# minimal_terminalv2.net
KiCad netlist of a schematic drawn in EAGLE
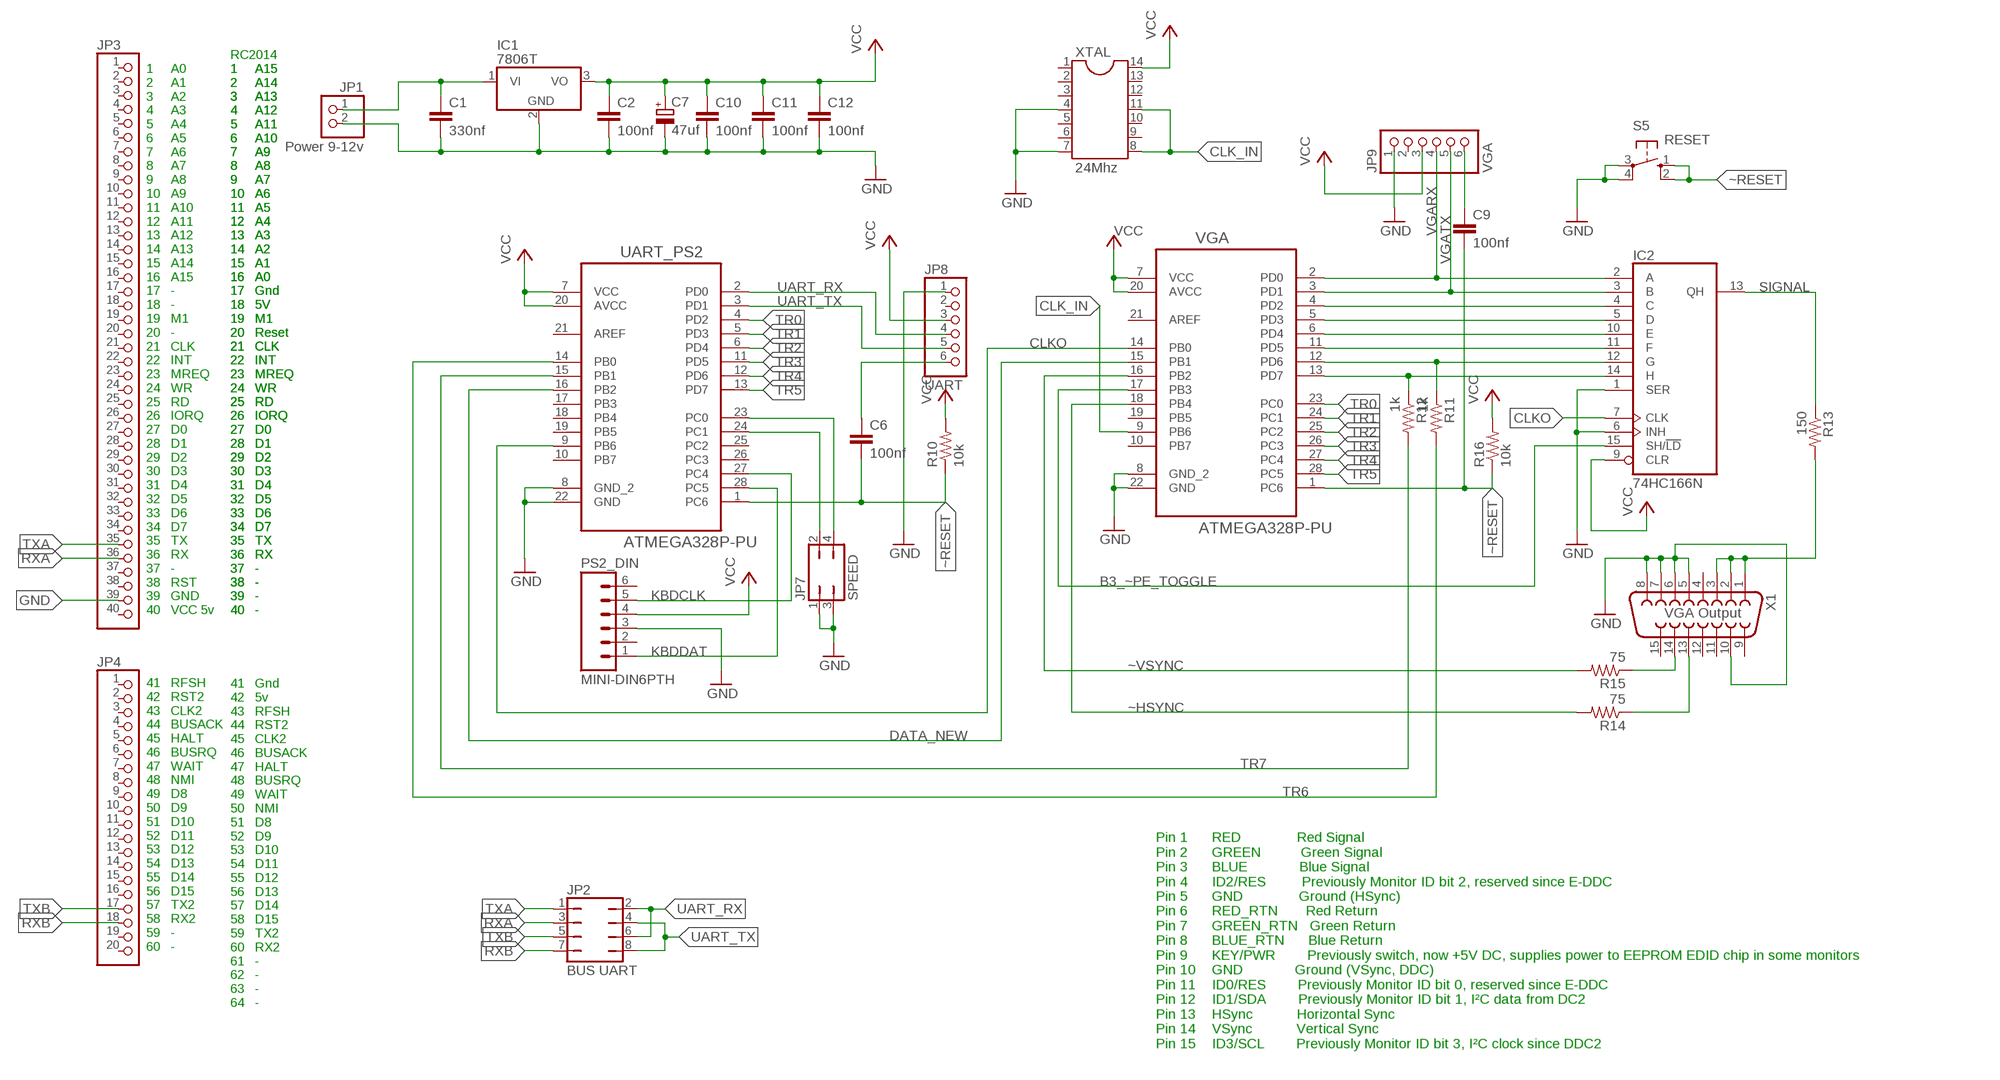
[diagram p0: schematic, sheet 1]

(export (version "E")
  (design (tool "Eeschema 10.0.6"))
  (components
    (comp (ref "C1")
      (value "330nf")
      (footprint "eagle-import:C2.5-3")
      (libsource (lib "eagle-import") (part "C2,5-3"))
    )
    (comp (ref "C2")
      (value "100nf")
      (footprint "eagle-import:C2.5-3")
      (libsource (lib "eagle-import") (part "C2,5-3"))
    )
    (comp (ref "C6")
      (value "100nf")
      (footprint "eagle-import:C2.5-3")
      (libsource (lib "eagle-import") (part "C2,5-3"))
    )
    (comp (ref "C7")
      (value "47uf")
      (footprint "eagle-import:E2,5-6")
      (libsource (lib "eagle-import") (part "CPOL-EUE2.5-6"))
    )
    (comp (ref "C9")
      (value "100nf")
      (footprint "eagle-import:C2.5-3")
      (libsource (lib "eagle-import") (part "C2,5-3"))
    )
    (comp (ref "C10")
      (value "100nf")
      (footprint "eagle-import:C2.5-3")
      (libsource (lib "eagle-import") (part "C2,5-3"))
    )
    (comp (ref "C11")
      (value "100nf")
      (footprint "eagle-import:C2.5-3")
      (libsource (lib "eagle-import") (part "C2,5-3"))
    )
    (comp (ref "C12")
      (value "100nf")
      (footprint "eagle-import:C2.5-3")
      (libsource (lib "eagle-import") (part "C2,5-3"))
    )
    (comp (ref "IC1")
      (value "7806T")
      (footprint "eagle-import:TO220H")
      (libsource (lib "eagle-import") (part "78T06"))
    )
    (comp (ref "IC2")
      (value "74HC166N")
      (footprint "eagle-import:DIL16")
      (libsource (lib "eagle-import") (part "74166NHC"))
    )
    (comp (ref "JP1")
      (value "Power 9-12v")
      (footprint "eagle-import:1X02")
      (libsource (lib "eagle-import") (part "PINHD-1X2"))
    )
    (comp (ref "JP2")
      (value "BUS UART")
      (footprint "eagle-import:JP4Q")
      (libsource (lib "eagle-import") (part "JP4Q"))
    )
    (comp (ref "JP3")
      (value "PINHD-1X40")
      (footprint "eagle-import:1X40")
      (libsource (lib "eagle-import") (part "PINHD-1X40"))
    )
    (comp (ref "JP4")
      (value "PINHD-1X20")
      (footprint "eagle-import:1X20")
      (libsource (lib "eagle-import") (part "PINHD-1X20"))
    )
    (comp (ref "JP7")
      (value "SPEED")
      (footprint "eagle-import:JP2Q")
      (libsource (lib "eagle-import") (part "JP2Q"))
    )
    (comp (ref "JP8")
      (value "UART")
      (footprint "eagle-import:1X06")
      (libsource (lib "eagle-import") (part "PINHD-1X6"))
    )
    (comp (ref "JP9")
      (value "VGA")
      (footprint "eagle-import:1X06")
      (libsource (lib "eagle-import") (part "PINHD-1X6"))
    )
    (comp (ref "PS2_DIN")
      (value "MINI-DIN6PTH")
      (footprint "eagle-import:MINI-DIN6")
      (libsource (lib "eagle-import") (part "MINI-DIN6PTH"))
    )
    (comp (ref "R10")
      (value "10k")
      (footprint "eagle-import:0204_7")
      (libsource (lib "eagle-import") (part "R-US_0204/7"))
    )
    (comp (ref "R11")
      (value "1k")
      (footprint "eagle-import:0204_7")
      (libsource (lib "eagle-import") (part "R-US_0204/7"))
    )
    (comp (ref "R12")
      (value "1k")
      (footprint "eagle-import:0204_7")
      (libsource (lib "eagle-import") (part "R-US_0204/7"))
    )
    (comp (ref "R13")
      (value "150")
      (footprint "eagle-import:0204_7")
      (libsource (lib "eagle-import") (part "R-US_0204/7"))
    )
    (comp (ref "R14")
      (value "75")
      (footprint "eagle-import:0204_7")
      (libsource (lib "eagle-import") (part "R-US_0204/7"))
    )
    (comp (ref "R15")
      (value "75")
      (footprint "eagle-import:0204_7")
      (libsource (lib "eagle-import") (part "R-US_0204/7"))
    )
    (comp (ref "R16")
      (value "10k")
      (footprint "eagle-import:0204_7")
      (libsource (lib "eagle-import") (part "R-US_0204/7"))
    )
    (comp (ref "S5")
      (value "RESET")
      (footprint "eagle-import:B3F-10XX")
      (fields (field (name "MPN") "B3F-1000"))
      (libsource (lib "eagle-import") (part "10-XX"))
    )
    (comp (ref "UART_PS2")
      (value "ATMEGA328P-PU")
      (footprint "eagle-import:DIP254P762X457-28")
      (libsource (lib "eagle-import") (part "ATMEGA328P-PU"))
    )
    (comp (ref "VGA")
      (value "ATMEGA328P-PU")
      (footprint "eagle-import:DIP254P762X457-28")
      (libsource (lib "eagle-import") (part "ATMEGA328P-PU"))
    )
    (comp (ref "X1")
      (value "VGA Output")
      (footprint "eagle-import:HDF15H")
      (libsource (lib "eagle-import") (part "F15HDH"))
    )
    (comp (ref "XTAL")
      (value "24Mhz")
      (footprint "eagle-import:SOCKET-14")
      (libsource (lib "eagle-import") (part "DIL14S"))
    )
  )
  (nets
    (net (code "1") (name "/B3_~{PE_TOGGLE}") (class "Default")
      (node (ref "IC2") (pin "15") (pinfunction "SH/~{LD}_15") (pintype "input"))
      (node (ref "VGA") (pin "17") (pinfunction "PB3_17") (pintype "bidirectional"))
    )
    (net (code "2") (name "/DATA_NEW") (class "Default")
      (node (ref "UART_PS2") (pin "16") (pinfunction "PB2_16") (pintype "bidirectional"))
      (node (ref "VGA") (pin "15") (pinfunction "PB1_15") (pintype "bidirectional"))
    )
    (net (code "3") (name "/KBDCLK") (class "Default")
      (node (ref "PS2_DIN") (pin "5") (pinfunction "5_5") (pintype "passive"))
      (node (ref "UART_PS2") (pin "27") (pinfunction "PC4_27") (pintype "bidirectional"))
    )
    (net (code "4") (name "/KBDDAT") (class "Default")
      (node (ref "PS2_DIN") (pin "1") (pinfunction "1_1") (pintype "passive"))
      (node (ref "UART_PS2") (pin "28") (pinfunction "PC5_28") (pintype "bidirectional"))
    )
    (net (code "5") (name "/SIGNAL") (class "Default")
      (node (ref "IC2") (pin "13") (pinfunction "QH_13") (pintype "output"))
      (node (ref "R13") (pin "1") (pinfunction "1_1") (pintype "passive"))
    )
    (net (code "6") (name "/TR6") (class "Default")
      (node (ref "R11") (pin "2") (pinfunction "2_2") (pintype "passive"))
      (node (ref "UART_PS2") (pin "14") (pinfunction "PB0_14") (pintype "bidirectional"))
    )
    (net (code "7") (name "/TR7") (class "Default")
      (node (ref "R12") (pin "2") (pinfunction "2_2") (pintype "passive"))
      (node (ref "UART_PS2") (pin "15") (pinfunction "PB1_15") (pintype "bidirectional"))
    )
    (net (code "8") (name "/VGARX") (class "Default")
      (node (ref "IC2") (pin "2") (pinfunction "A_2") (pintype "input"))
      (node (ref "JP9") (pin "4") (pinfunction "4_4") (pintype "passive"))
      (node (ref "VGA") (pin "2") (pinfunction "PD0_2") (pintype "bidirectional"))
    )
    (net (code "9") (name "/VGATX") (class "Default")
      (node (ref "IC2") (pin "3") (pinfunction "B_3") (pintype "input"))
      (node (ref "JP9") (pin "5") (pinfunction "5_5") (pintype "passive"))
      (node (ref "VGA") (pin "3") (pinfunction "PD1_3") (pintype "bidirectional"))
    )
    (net (code "10") (name "/~{HSYNC}") (class "Default")
      (node (ref "R14") (pin "2") (pinfunction "2_2") (pintype "passive"))
      (node (ref "VGA") (pin "18") (pinfunction "PB4_18") (pintype "bidirectional"))
    )
    (net (code "11") (name "/~{RESET}") (class "Default")
      (node (ref "C6") (pin "2") (pinfunction "2_2") (pintype "passive"))
      (node (ref "C9") (pin "2") (pinfunction "2_2") (pintype "passive"))
      (node (ref "R10") (pin "1") (pinfunction "1_1") (pintype "passive"))
      (node (ref "R16") (pin "1") (pinfunction "1_1") (pintype "passive"))
      (node (ref "S5") (pin "1") (pinfunction "S_1") (pintype "passive"))
      (node (ref "S5") (pin "2") (pinfunction "S1_2") (pintype "passive"))
      (node (ref "UART_PS2") (pin "1") (pinfunction "PC6_1") (pintype "bidirectional"))
      (node (ref "VGA") (pin "1") (pinfunction "PC6_1") (pintype "bidirectional"))
    )
    (net (code "12") (name "/~{VSYNC}") (class "Default")
      (node (ref "R15") (pin "2") (pinfunction "2_2") (pintype "passive"))
      (node (ref "VGA") (pin "16") (pinfunction "PB2_16") (pintype "bidirectional"))
    )
    (net (code "13") (name "CLKO") (class "Default")
      (node (ref "IC2") (pin "7") (pinfunction "CLK_7") (pintype "input"))
      (node (ref "UART_PS2") (pin "9") (pinfunction "PB6_9") (pintype "bidirectional"))
      (node (ref "VGA") (pin "14") (pinfunction "PB0_14") (pintype "bidirectional"))
    )
    (net (code "14") (name "CLK_IN") (class "Default")
      (node (ref "VGA") (pin "9") (pinfunction "PB6_9") (pintype "bidirectional"))
      (node (ref "XTAL") (pin "11") (pinfunction "11_11") (pintype "passive"))
      (node (ref "XTAL") (pin "8") (pinfunction "8_8") (pintype "passive"))
    )
    (net (code "15") (name "GND") (class "Default")
      (node (ref "C1") (pin "2") (pinfunction "2_2") (pintype "passive"))
      (node (ref "C10") (pin "2") (pinfunction "2_2") (pintype "passive"))
      (node (ref "C11") (pin "2") (pinfunction "2_2") (pintype "passive"))
      (node (ref "C12") (pin "2") (pinfunction "2_2") (pintype "passive"))
      (node (ref "C2") (pin "2") (pinfunction "2_2") (pintype "passive"))
      (node (ref "C7") (pin "-") (pinfunction "-_-") (pintype "passive"))
      (node (ref "IC1") (pin "2") (pinfunction "GND_2") (pintype "passive"))
      (node (ref "IC2") (pin "1") (pinfunction "SER_1") (pintype "input"))
      (node (ref "IC2") (pin "6") (pinfunction "INH_6") (pintype "input"))
      (node (ref "JP1") (pin "2") (pinfunction "2_2") (pintype "passive"))
      (node (ref "JP3") (pin "39") (pinfunction "39_39") (pintype "passive"))
      (node (ref "JP7") (pin "1") (pinfunction "1_1") (pintype "passive"))
      (node (ref "JP7") (pin "3") (pinfunction "3_3") (pintype "passive"))
      (node (ref "JP8") (pin "1") (pinfunction "1_1") (pintype "passive"))
      (node (ref "JP9") (pin "1") (pinfunction "1_1") (pintype "passive"))
      (node (ref "PS2_DIN") (pin "3") (pinfunction "3_3") (pintype "passive"))
      (node (ref "S5") (pin "3") (pinfunction "P_3") (pintype "passive"))
      (node (ref "S5") (pin "4") (pinfunction "P1_4") (pintype "passive"))
      (node (ref "UART_PS2") (pin "22") (pinfunction "GND_22") (pintype "passive"))
      (node (ref "UART_PS2") (pin "8") (pinfunction "GND_2_8") (pintype "passive"))
      (node (ref "VGA") (pin "22") (pinfunction "GND_22") (pintype "passive"))
      (node (ref "VGA") (pin "8") (pinfunction "GND_2_8") (pintype "passive"))
      (node (ref "X1") (pin "10") (pinfunction "10_10") (pintype "passive"))
      (node (ref "X1") (pin "5") (pinfunction "5_5") (pintype "passive"))
      (node (ref "X1") (pin "6") (pinfunction "6_6") (pintype "passive"))
      (node (ref "X1") (pin "7") (pinfunction "7_7") (pintype "passive"))
      (node (ref "X1") (pin "8") (pinfunction "8_8") (pintype "passive"))
      (node (ref "XTAL") (pin "4") (pinfunction "4_4") (pintype "passive"))
      (node (ref "XTAL") (pin "7") (pinfunction "7_7") (pintype "passive"))
    )
    (net (code "16") (name "Net-(C6-Pad1)") (class "Default")
      (node (ref "C6") (pin "1") (pinfunction "1_1") (pintype "passive"))
      (node (ref "JP8") (pin "6") (pinfunction "6_6") (pintype "passive"))
    )
    (net (code "17") (name "Net-(C9-Pad1)") (class "Default")
      (node (ref "C9") (pin "1") (pinfunction "1_1") (pintype "passive"))
      (node (ref "JP9") (pin "6") (pinfunction "6_6") (pintype "passive"))
    )
    (net (code "18") (name "Net-(IC1-VI)") (class "Default")
      (node (ref "C1") (pin "1") (pinfunction "1_1") (pintype "passive"))
      (node (ref "IC1") (pin "1") (pinfunction "VI_1") (pintype "input"))
      (node (ref "JP1") (pin "1") (pinfunction "1_1") (pintype "passive"))
    )
    (net (code "19") (name "Net-(IC2A-C)") (class "Default")
      (node (ref "IC2") (pin "4") (pinfunction "C_4") (pintype "input"))
      (node (ref "VGA") (pin "4") (pinfunction "PD2_4") (pintype "bidirectional"))
    )
    (net (code "20") (name "Net-(IC2A-D)") (class "Default")
      (node (ref "IC2") (pin "5") (pinfunction "D_5") (pintype "input"))
      (node (ref "VGA") (pin "5") (pinfunction "PD3_5") (pintype "bidirectional"))
    )
    (net (code "21") (name "Net-(IC2A-E)") (class "Default")
      (node (ref "IC2") (pin "10") (pinfunction "E_10") (pintype "input"))
      (node (ref "VGA") (pin "6") (pinfunction "PD4_6") (pintype "bidirectional"))
    )
    (net (code "22") (name "Net-(IC2A-F)") (class "Default")
      (node (ref "IC2") (pin "11") (pinfunction "F_11") (pintype "input"))
      (node (ref "VGA") (pin "11") (pinfunction "PD5_11") (pintype "bidirectional"))
    )
    (net (code "23") (name "Net-(IC2A-G)") (class "Default")
      (node (ref "IC2") (pin "12") (pinfunction "G_12") (pintype "input"))
      (node (ref "R11") (pin "1") (pinfunction "1_1") (pintype "passive"))
      (node (ref "VGA") (pin "12") (pinfunction "PD6_12") (pintype "bidirectional"))
    )
    (net (code "24") (name "Net-(IC2A-H)") (class "Default")
      (node (ref "IC2") (pin "14") (pinfunction "H_14") (pintype "input"))
      (node (ref "R12") (pin "1") (pinfunction "1_1") (pintype "passive"))
      (node (ref "VGA") (pin "13") (pinfunction "PD7_13") (pintype "bidirectional"))
    )
    (net (code "25") (name "Net-(R13-Pad2)") (class "Default")
      (node (ref "R13") (pin "2") (pinfunction "2_2") (pintype "passive"))
      (node (ref "X1") (pin "1") (pinfunction "1_1") (pintype "passive"))
      (node (ref "X1") (pin "2") (pinfunction "2_2") (pintype "passive"))
      (node (ref "X1") (pin "3") (pinfunction "3_3") (pintype "passive"))
    )
    (net (code "26") (name "Net-(R14-Pad1)") (class "Default")
      (node (ref "R14") (pin "1") (pinfunction "1_1") (pintype "passive"))
      (node (ref "X1") (pin "13") (pinfunction "13_13") (pintype "passive"))
    )
    (net (code "27") (name "Net-(R15-Pad1)") (class "Default")
      (node (ref "R15") (pin "1") (pinfunction "1_1") (pintype "passive"))
      (node (ref "X1") (pin "14") (pinfunction "14_14") (pintype "passive"))
    )
    (net (code "28") (name "Net-(UART_PS2-PC0)") (class "Default")
      (node (ref "JP7") (pin "4") (pinfunction "4_4") (pintype "passive"))
      (node (ref "UART_PS2") (pin "23") (pinfunction "PC0_23") (pintype "bidirectional"))
    )
    (net (code "29") (name "Net-(UART_PS2-PC1)") (class "Default")
      (node (ref "JP7") (pin "2") (pinfunction "2_2") (pintype "passive"))
      (node (ref "UART_PS2") (pin "24") (pinfunction "PC1_24") (pintype "bidirectional"))
    )
    (net (code "30") (name "RXA") (class "Default")
      (node (ref "JP2") (pin "3") (pinfunction "3_3") (pintype "passive"))
      (node (ref "JP3") (pin "36") (pinfunction "36_36") (pintype "passive"))
    )
    (net (code "31") (name "RXB") (class "Default")
      (node (ref "JP2") (pin "7") (pinfunction "7_7") (pintype "passive"))
      (node (ref "JP4") (pin "18") (pinfunction "18_18") (pintype "passive"))
    )
    (net (code "32") (name "TR0") (class "Default")
      (node (ref "UART_PS2") (pin "4") (pinfunction "PD2_4") (pintype "bidirectional"))
      (node (ref "VGA") (pin "23") (pinfunction "PC0_23") (pintype "bidirectional"))
    )
    (net (code "33") (name "TR1") (class "Default")
      (node (ref "UART_PS2") (pin "5") (pinfunction "PD3_5") (pintype "bidirectional"))
      (node (ref "VGA") (pin "24") (pinfunction "PC1_24") (pintype "bidirectional"))
    )
    (net (code "34") (name "TR2") (class "Default")
      (node (ref "UART_PS2") (pin "6") (pinfunction "PD4_6") (pintype "bidirectional"))
      (node (ref "VGA") (pin "25") (pinfunction "PC2_25") (pintype "bidirectional"))
    )
    (net (code "35") (name "TR3") (class "Default")
      (node (ref "UART_PS2") (pin "11") (pinfunction "PD5_11") (pintype "bidirectional"))
      (node (ref "VGA") (pin "26") (pinfunction "PC3_26") (pintype "bidirectional"))
    )
    (net (code "36") (name "TR4") (class "Default")
      (node (ref "UART_PS2") (pin "12") (pinfunction "PD6_12") (pintype "bidirectional"))
      (node (ref "VGA") (pin "27") (pinfunction "PC4_27") (pintype "bidirectional"))
    )
    (net (code "37") (name "TR5") (class "Default")
      (node (ref "UART_PS2") (pin "13") (pinfunction "PD7_13") (pintype "bidirectional"))
      (node (ref "VGA") (pin "28") (pinfunction "PC5_28") (pintype "bidirectional"))
    )
    (net (code "38") (name "TXA") (class "Default")
      (node (ref "JP2") (pin "1") (pinfunction "1_1") (pintype "passive"))
      (node (ref "JP3") (pin "35") (pinfunction "35_35") (pintype "passive"))
    )
    (net (code "39") (name "TXB") (class "Default")
      (node (ref "JP2") (pin "5") (pinfunction "5_5") (pintype "passive"))
      (node (ref "JP4") (pin "17") (pinfunction "17_17") (pintype "passive"))
    )
    (net (code "40") (name "UART_RX") (class "Default")
      (node (ref "JP2") (pin "2") (pinfunction "2_2") (pintype "passive"))
      (node (ref "JP2") (pin "6") (pinfunction "6_6") (pintype "passive"))
      (node (ref "JP8") (pin "4") (pinfunction "4_4") (pintype "passive"))
      (node (ref "UART_PS2") (pin "2") (pinfunction "PD0_2") (pintype "bidirectional"))
    )
    (net (code "41") (name "UART_TX") (class "Default")
      (node (ref "JP2") (pin "4") (pinfunction "4_4") (pintype "passive"))
      (node (ref "JP2") (pin "8") (pinfunction "8_8") (pintype "passive"))
      (node (ref "JP8") (pin "5") (pinfunction "5_5") (pintype "passive"))
      (node (ref "UART_PS2") (pin "3") (pinfunction "PD1_3") (pintype "bidirectional"))
    )
    (net (code "42") (name "VCC") (class "Default")
      (node (ref "C10") (pin "1") (pinfunction "1_1") (pintype "passive"))
      (node (ref "C11") (pin "1") (pinfunction "1_1") (pintype "passive"))
      (node (ref "C12") (pin "1") (pinfunction "1_1") (pintype "passive"))
      (node (ref "C2") (pin "1") (pinfunction "1_1") (pintype "passive"))
      (node (ref "C7") (pin "+") (pinfunction "+_+") (pintype "passive"))
      (node (ref "IC1") (pin "3") (pinfunction "VO_3") (pintype "passive"))
      (node (ref "IC2") (pin "9") (pinfunction "CLR_9") (pintype "input"))
      (node (ref "JP8") (pin "3") (pinfunction "3_3") (pintype "passive"))
      (node (ref "JP9") (pin "3") (pinfunction "3_3") (pintype "passive"))
      (node (ref "PS2_DIN") (pin "4") (pinfunction "4_4") (pintype "passive"))
      (node (ref "R10") (pin "2") (pinfunction "2_2") (pintype "passive"))
      (node (ref "R16") (pin "2") (pinfunction "2_2") (pintype "passive"))
      (node (ref "UART_PS2") (pin "20") (pinfunction "AVCC_20") (pintype "power_in"))
      (node (ref "UART_PS2") (pin "7") (pinfunction "VCC_7") (pintype "power_in"))
      (node (ref "VGA") (pin "20") (pinfunction "AVCC_20") (pintype "power_in"))
      (node (ref "VGA") (pin "7") (pinfunction "VCC_7") (pintype "power_in"))
      (node (ref "XTAL") (pin "14") (pinfunction "14_14") (pintype "passive"))
    )
    (net (code "43") (name "unconnected-(JP3-Pad1)") (class "Default")
      (node (ref "JP3") (pin "1") (pinfunction "1_1") (pintype "passive"))
    )
    (net (code "44") (name "unconnected-(JP3-Pad2)") (class "Default")
      (node (ref "JP3") (pin "2") (pinfunction "2_2") (pintype "passive"))
    )
    (net (code "45") (name "unconnected-(JP3-Pad3)") (class "Default")
      (node (ref "JP3") (pin "3") (pinfunction "3_3") (pintype "passive"))
    )
    (net (code "46") (name "unconnected-(JP3-Pad4)") (class "Default")
      (node (ref "JP3") (pin "4") (pinfunction "4_4") (pintype "passive"))
    )
    (net (code "47") (name "unconnected-(JP3-Pad5)") (class "Default")
      (node (ref "JP3") (pin "5") (pinfunction "5_5") (pintype "passive"))
    )
    (net (code "48") (name "unconnected-(JP3-Pad6)") (class "Default")
      (node (ref "JP3") (pin "6") (pinfunction "6_6") (pintype "passive"))
    )
    (net (code "49") (name "unconnected-(JP3-Pad7)") (class "Default")
      (node (ref "JP3") (pin "7") (pinfunction "7_7") (pintype "passive"))
    )
    (net (code "50") (name "unconnected-(JP3-Pad8)") (class "Default")
      (node (ref "JP3") (pin "8") (pinfunction "8_8") (pintype "passive"))
    )
    (net (code "51") (name "unconnected-(JP3-Pad9)") (class "Default")
      (node (ref "JP3") (pin "9") (pinfunction "9_9") (pintype "passive"))
    )
    (net (code "52") (name "unconnected-(JP3-Pad10)") (class "Default")
      (node (ref "JP3") (pin "10") (pinfunction "10_10") (pintype "passive"))
    )
    (net (code "53") (name "unconnected-(JP3-Pad11)") (class "Default")
      (node (ref "JP3") (pin "11") (pinfunction "11_11") (pintype "passive"))
    )
    (net (code "54") (name "unconnected-(JP3-Pad12)") (class "Default")
      (node (ref "JP3") (pin "12") (pinfunction "12_12") (pintype "passive"))
    )
    (net (code "55") (name "unconnected-(JP3-Pad13)") (class "Default")
      (node (ref "JP3") (pin "13") (pinfunction "13_13") (pintype "passive"))
    )
    (net (code "56") (name "unconnected-(JP3-Pad14)") (class "Default")
      (node (ref "JP3") (pin "14") (pinfunction "14_14") (pintype "passive"))
    )
    (net (code "57") (name "unconnected-(JP3-Pad15)") (class "Default")
      (node (ref "JP3") (pin "15") (pinfunction "15_15") (pintype "passive"))
    )
    (net (code "58") (name "unconnected-(JP3-Pad16)") (class "Default")
      (node (ref "JP3") (pin "16") (pinfunction "16_16") (pintype "passive"))
    )
    (net (code "59") (name "unconnected-(JP3-Pad17)") (class "Default")
      (node (ref "JP3") (pin "17") (pinfunction "17_17") (pintype "passive"))
    )
    (net (code "60") (name "unconnected-(JP3-Pad18)") (class "Default")
      (node (ref "JP3") (pin "18") (pinfunction "18_18") (pintype "passive"))
    )
    (net (code "61") (name "unconnected-(JP3-Pad19)") (class "Default")
      (node (ref "JP3") (pin "19") (pinfunction "19_19") (pintype "passive"))
    )
    (net (code "62") (name "unconnected-(JP3-Pad20)") (class "Default")
      (node (ref "JP3") (pin "20") (pinfunction "20_20") (pintype "passive"))
    )
    (net (code "63") (name "unconnected-(JP3-Pad21)") (class "Default")
      (node (ref "JP3") (pin "21") (pinfunction "21_21") (pintype "passive"))
    )
    (net (code "64") (name "unconnected-(JP3-Pad22)") (class "Default")
      (node (ref "JP3") (pin "22") (pinfunction "22_22") (pintype "passive"))
    )
    (net (code "65") (name "unconnected-(JP3-Pad23)") (class "Default")
      (node (ref "JP3") (pin "23") (pinfunction "23_23") (pintype "passive"))
    )
    (net (code "66") (name "unconnected-(JP3-Pad24)") (class "Default")
      (node (ref "JP3") (pin "24") (pinfunction "24_24") (pintype "passive"))
    )
    (net (code "67") (name "unconnected-(JP3-Pad25)") (class "Default")
      (node (ref "JP3") (pin "25") (pinfunction "25_25") (pintype "passive"))
    )
    (net (code "68") (name "unconnected-(JP3-Pad26)") (class "Default")
      (node (ref "JP3") (pin "26") (pinfunction "26_26") (pintype "passive"))
    )
    (net (code "69") (name "unconnected-(JP3-Pad27)") (class "Default")
      (node (ref "JP3") (pin "27") (pinfunction "27_27") (pintype "passive"))
    )
    (net (code "70") (name "unconnected-(JP3-Pad28)") (class "Default")
      (node (ref "JP3") (pin "28") (pinfunction "28_28") (pintype "passive"))
    )
    (net (code "71") (name "unconnected-(JP3-Pad29)") (class "Default")
      (node (ref "JP3") (pin "29") (pinfunction "29_29") (pintype "passive"))
    )
    (net (code "72") (name "unconnected-(JP3-Pad30)") (class "Default")
      (node (ref "JP3") (pin "30") (pinfunction "30_30") (pintype "passive"))
    )
    (net (code "73") (name "unconnected-(JP3-Pad31)") (class "Default")
      (node (ref "JP3") (pin "31") (pinfunction "31_31") (pintype "passive"))
    )
    (net (code "74") (name "unconnected-(JP3-Pad32)") (class "Default")
      (node (ref "JP3") (pin "32") (pinfunction "32_32") (pintype "passive"))
    )
    (net (code "75") (name "unconnected-(JP3-Pad33)") (class "Default")
      (node (ref "JP3") (pin "33") (pinfunction "33_33") (pintype "passive"))
    )
    (net (code "76") (name "unconnected-(JP3-Pad34)") (class "Default")
      (node (ref "JP3") (pin "34") (pinfunction "34_34") (pintype "passive"))
    )
    (net (code "77") (name "unconnected-(JP3-Pad37)") (class "Default")
      (node (ref "JP3") (pin "37") (pinfunction "37_37") (pintype "passive"))
    )
    (net (code "78") (name "unconnected-(JP3-Pad38)") (class "Default")
      (node (ref "JP3") (pin "38") (pinfunction "38_38") (pintype "passive"))
    )
    (net (code "79") (name "unconnected-(JP3-Pad40)") (class "Default")
      (node (ref "JP3") (pin "40") (pinfunction "40_40") (pintype "passive"))
    )
    (net (code "80") (name "unconnected-(JP4-Pad1)") (class "Default")
      (node (ref "JP4") (pin "1") (pinfunction "1_1") (pintype "passive"))
    )
    (net (code "81") (name "unconnected-(JP4-Pad2)") (class "Default")
      (node (ref "JP4") (pin "2") (pinfunction "2_2") (pintype "passive"))
    )
    (net (code "82") (name "unconnected-(JP4-Pad3)") (class "Default")
      (node (ref "JP4") (pin "3") (pinfunction "3_3") (pintype "passive"))
    )
    (net (code "83") (name "unconnected-(JP4-Pad4)") (class "Default")
      (node (ref "JP4") (pin "4") (pinfunction "4_4") (pintype "passive"))
    )
    (net (code "84") (name "unconnected-(JP4-Pad5)") (class "Default")
      (node (ref "JP4") (pin "5") (pinfunction "5_5") (pintype "passive"))
    )
    (net (code "85") (name "unconnected-(JP4-Pad6)") (class "Default")
      (node (ref "JP4") (pin "6") (pinfunction "6_6") (pintype "passive"))
    )
    (net (code "86") (name "unconnected-(JP4-Pad7)") (class "Default")
      (node (ref "JP4") (pin "7") (pinfunction "7_7") (pintype "passive"))
    )
    (net (code "87") (name "unconnected-(JP4-Pad8)") (class "Default")
      (node (ref "JP4") (pin "8") (pinfunction "8_8") (pintype "passive"))
    )
    (net (code "88") (name "unconnected-(JP4-Pad9)") (class "Default")
      (node (ref "JP4") (pin "9") (pinfunction "9_9") (pintype "passive"))
    )
    (net (code "89") (name "unconnected-(JP4-Pad10)") (class "Default")
      (node (ref "JP4") (pin "10") (pinfunction "10_10") (pintype "passive"))
    )
    (net (code "90") (name "unconnected-(JP4-Pad11)") (class "Default")
      (node (ref "JP4") (pin "11") (pinfunction "11_11") (pintype "passive"))
    )
    (net (code "91") (name "unconnected-(JP4-Pad12)") (class "Default")
      (node (ref "JP4") (pin "12") (pinfunction "12_12") (pintype "passive"))
    )
    (net (code "92") (name "unconnected-(JP4-Pad13)") (class "Default")
      (node (ref "JP4") (pin "13") (pinfunction "13_13") (pintype "passive"))
    )
    (net (code "93") (name "unconnected-(JP4-Pad14)") (class "Default")
      (node (ref "JP4") (pin "14") (pinfunction "14_14") (pintype "passive"))
    )
    (net (code "94") (name "unconnected-(JP4-Pad15)") (class "Default")
      (node (ref "JP4") (pin "15") (pinfunction "15_15") (pintype "passive"))
    )
    (net (code "95") (name "unconnected-(JP4-Pad16)") (class "Default")
      (node (ref "JP4") (pin "16") (pinfunction "16_16") (pintype "passive"))
    )
    (net (code "96") (name "unconnected-(JP4-Pad19)") (class "Default")
      (node (ref "JP4") (pin "19") (pinfunction "19_19") (pintype "passive"))
    )
    (net (code "97") (name "unconnected-(JP4-Pad20)") (class "Default")
      (node (ref "JP4") (pin "20") (pinfunction "20_20") (pintype "passive"))
    )
    (net (code "98") (name "unconnected-(JP8-Pad2)") (class "Default")
      (node (ref "JP8") (pin "2") (pinfunction "2_2") (pintype "passive"))
    )
    (net (code "99") (name "unconnected-(JP9-Pad2)") (class "Default")
      (node (ref "JP9") (pin "2") (pinfunction "2_2") (pintype "passive"))
    )
    (net (code "100") (name "unconnected-(PS2_DIN-Pad2)") (class "Default")
      (node (ref "PS2_DIN") (pin "2") (pinfunction "2_2") (pintype "passive"))
    )
    (net (code "101") (name "unconnected-(PS2_DIN-Pad6)") (class "Default")
      (node (ref "PS2_DIN") (pin "6") (pinfunction "6_6") (pintype "passive"))
    )
    (net (code "102") (name "unconnected-(UART_PS2-AREF-Pad21)") (class "Default")
      (node (ref "UART_PS2") (pin "21") (pinfunction "AREF_21") (pintype "input"))
    )
    (net (code "103") (name "unconnected-(UART_PS2-PB3-Pad17)") (class "Default")
      (node (ref "UART_PS2") (pin "17") (pinfunction "PB3_17") (pintype "bidirectional"))
    )
    (net (code "104") (name "unconnected-(UART_PS2-PB4-Pad18)") (class "Default")
      (node (ref "UART_PS2") (pin "18") (pinfunction "PB4_18") (pintype "bidirectional"))
    )
    (net (code "105") (name "unconnected-(UART_PS2-PB5-Pad19)") (class "Default")
      (node (ref "UART_PS2") (pin "19") (pinfunction "PB5_19") (pintype "bidirectional"))
    )
    (net (code "106") (name "unconnected-(UART_PS2-PB7-Pad10)") (class "Default")
      (node (ref "UART_PS2") (pin "10") (pinfunction "PB7_10") (pintype "bidirectional"))
    )
    (net (code "107") (name "unconnected-(UART_PS2-PC2-Pad25)") (class "Default")
      (node (ref "UART_PS2") (pin "25") (pinfunction "PC2_25") (pintype "bidirectional"))
    )
    (net (code "108") (name "unconnected-(UART_PS2-PC3-Pad26)") (class "Default")
      (node (ref "UART_PS2") (pin "26") (pinfunction "PC3_26") (pintype "bidirectional"))
    )
    (net (code "109") (name "unconnected-(VGA-AREF-Pad21)") (class "Default")
      (node (ref "VGA") (pin "21") (pinfunction "AREF_21") (pintype "input"))
    )
    (net (code "110") (name "unconnected-(VGA-PB5-Pad19)") (class "Default")
      (node (ref "VGA") (pin "19") (pinfunction "PB5_19") (pintype "bidirectional"))
    )
    (net (code "111") (name "unconnected-(VGA-PB7-Pad10)") (class "Default")
      (node (ref "VGA") (pin "10") (pinfunction "PB7_10") (pintype "bidirectional"))
    )
    (net (code "112") (name "unconnected-(X1-Pad4)") (class "Default")
      (node (ref "X1") (pin "4") (pinfunction "4_4") (pintype "passive"))
    )
    (net (code "113") (name "unconnected-(X1-Pad9)") (class "Default")
      (node (ref "X1") (pin "9") (pinfunction "9_9") (pintype "passive"))
    )
    (net (code "114") (name "unconnected-(X1-Pad11)") (class "Default")
      (node (ref "X1") (pin "11") (pinfunction "11_11") (pintype "passive"))
    )
    (net (code "115") (name "unconnected-(X1-Pad12)") (class "Default")
      (node (ref "X1") (pin "12") (pinfunction "12_12") (pintype "passive"))
    )
    (net (code "116") (name "unconnected-(X1-Pad15)") (class "Default")
      (node (ref "X1") (pin "15") (pinfunction "15_15") (pintype "passive"))
    )
    (net (code "117") (name "unconnected-(XTAL-Pad1)") (class "Default")
      (node (ref "XTAL") (pin "1") (pinfunction "1_1") (pintype "passive"))
    )
    (net (code "118") (name "unconnected-(XTAL-Pad2)") (class "Default")
      (node (ref "XTAL") (pin "2") (pinfunction "2_2") (pintype "passive"))
    )
    (net (code "119") (name "unconnected-(XTAL-Pad3)") (class "Default")
      (node (ref "XTAL") (pin "3") (pinfunction "3_3") (pintype "passive"))
    )
    (net (code "120") (name "unconnected-(XTAL-Pad5)") (class "Default")
      (node (ref "XTAL") (pin "5") (pinfunction "5_5") (pintype "passive"))
    )
    (net (code "121") (name "unconnected-(XTAL-Pad6)") (class "Default")
      (node (ref "XTAL") (pin "6") (pinfunction "6_6") (pintype "passive"))
    )
    (net (code "122") (name "unconnected-(XTAL-Pad9)") (class "Default")
      (node (ref "XTAL") (pin "9") (pinfunction "9_9") (pintype "passive"))
    )
    (net (code "123") (name "unconnected-(XTAL-Pad10)") (class "Default")
      (node (ref "XTAL") (pin "10") (pinfunction "10_10") (pintype "passive"))
    )
    (net (code "124") (name "unconnected-(XTAL-Pad12)") (class "Default")
      (node (ref "XTAL") (pin "12") (pinfunction "12_12") (pintype "passive"))
    )
    (net (code "125") (name "unconnected-(XTAL-Pad13)") (class "Default")
      (node (ref "XTAL") (pin "13") (pinfunction "13_13") (pintype "passive"))
    )
  )
)
